# Oscillator.net
KiCad netlist of a schematic drawn in Altium Designer
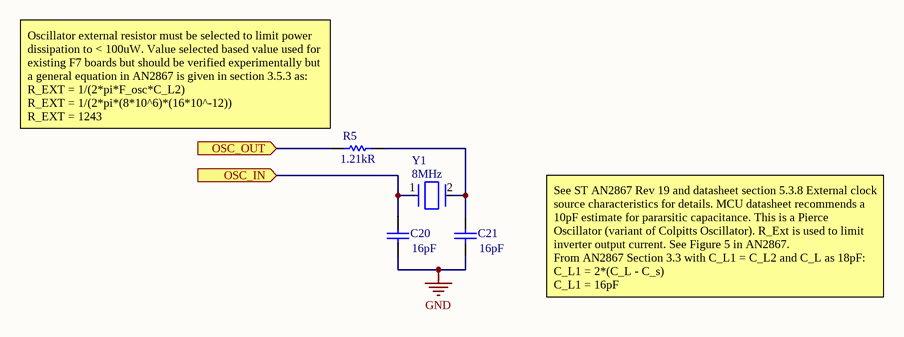
[diagram p0: Oscillator.SchDoc]

(export (version "E")
  (design (tool "Eeschema 10.0.6"))
  (components
    (comp (ref "C20")
      (value "06035A160JAT2A")
      (footprint "CAPC1608X90X35ML15T15")
      (fields (field (name "MANUFACTURER") "AVX Interconnect / Elco") (field (name "CAPACITANCE") "16pF"))
      (libsource (lib "Altium Content Vault") (part "CAP"))
    )
    (comp (ref "C21")
      (value "06035A160JAT2A")
      (footprint "CAPC1608X90X35ML15T15")
      (fields (field (name "MANUFACTURER") "AVX Interconnect / Elco") (field (name "CAPACITANCE") "16pF"))
      (libsource (lib "Altium Content Vault") (part "CAP"))
    )
    (comp (ref "R5")
      (value "CR0402-FX-1211GLF")
      (footprint "RESC1005X40X25NL10T10")
      (fields (field (name "MANUFACTURER") "Bourns") (field (name "RESISTANCE") "1.21kR"))
      (libsource (lib "Altium Content Vault") (part "RES"))
    )
    (comp (ref "Y1")
      (value "ABM3-8.000MHZ-D2Y-T")
      (footprint "FP-ABM3-MFG")
      (description "Crystal 8MHz ±20ppm 18pF SMD-2 5mm x 3.2mm")
      (fields (field (name "TOLERANCE") "20ppm") (field (name "FREQUENCY") "8MHz"))
      (libsource (lib "Altium Content Vault") (part "c23a69dc6c9e2f18f2079038eb95dd1"))
    )
  )
  (nets
    (net (code "1") (name "/OSC_IN") (class "Default")
      (node (ref "C20") (pin "2") (pinfunction "2_2") (pintype "passive"))
      (node (ref "Y1") (pin "1") (pinfunction "1_1") (pintype "passive"))
    )
    (net (code "2") (name "/OSC_OUT") (class "Default")
      (node (ref "R5") (pin "1") (pinfunction "1_1") (pintype "passive"))
    )
    (net (code "3") (name "GND") (class "Default")
      (node (ref "C20") (pin "1") (pinfunction "1_1") (pintype "passive"))
      (node (ref "C21") (pin "1") (pinfunction "1_1") (pintype "passive"))
    )
    (net (code "4") (name "Net-(C21-Pad2)") (class "Default")
      (node (ref "C21") (pin "2") (pinfunction "2_2") (pintype "passive"))
      (node (ref "R5") (pin "2") (pinfunction "2_2") (pintype "passive"))
      (node (ref "Y1") (pin "2") (pinfunction "2_2") (pintype "passive"))
    )
  )
)
